# supply.net
KiCad netlist of a schematic drawn in Altium Designer
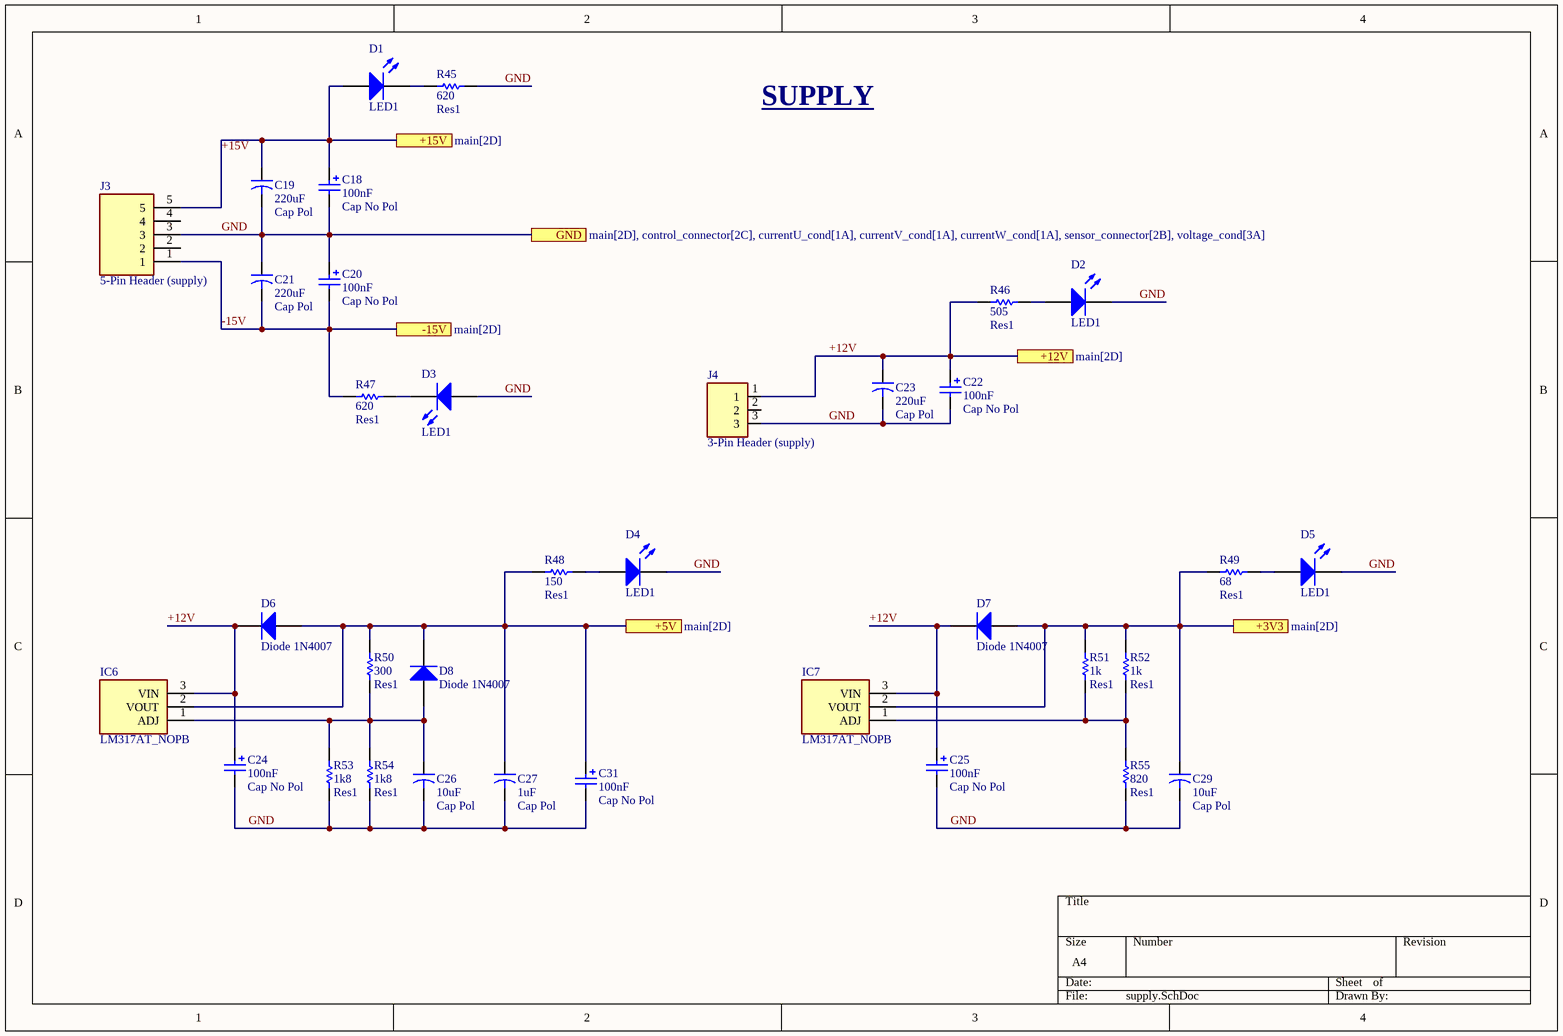
[diagram p0: supply.SchDoc]

(export (version "E")
  (design (tool "Eeschema 10.0.6"))
  (components
    (comp (ref "C18")
      (value "Cap No Pol")
      (footprint "RAD-0.1_mod")
      (description "Polarized Capacitor (Radial)")
      (fields (field (name "ALTIUM_VALUE") "100nF") (field (name "PUBLISHER") "Altium Limited"))
      (libsource (lib "LABSTEPS_Project") (part "Cap No Pol"))
    )
    (comp (ref "C19")
      (value "Cap Pol")
      (footprint "CAPR5-4X5_mod")
      (description "Capacitor")
      (fields (field (name "ALTIUM_VALUE") "220uF") (field (name "PUBLISHER") "Altium Limited"))
      (libsource (lib "LABSTEPS_Project") (part "Cap Pol"))
    )
    (comp (ref "C20")
      (value "Cap No Pol")
      (footprint "RAD-0.1_mod")
      (description "Polarized Capacitor (Radial)")
      (fields (field (name "ALTIUM_VALUE") "100nF") (field (name "PUBLISHER") "Altium Limited"))
      (libsource (lib "LABSTEPS_Project") (part "Cap No Pol"))
    )
    (comp (ref "C21")
      (value "Cap Pol")
      (footprint "CAPR5-4X5_mod")
      (description "Capacitor")
      (fields (field (name "ALTIUM_VALUE") "220uF") (field (name "PUBLISHER") "Altium Limited"))
      (libsource (lib "LABSTEPS_Project") (part "Cap Pol"))
    )
    (comp (ref "C22")
      (value "Cap No Pol")
      (footprint "RAD-0.1_mod")
      (description "Polarized Capacitor (Radial)")
      (fields (field (name "ALTIUM_VALUE") "100nF") (field (name "PUBLISHER") "Altium Limited"))
      (libsource (lib "LABSTEPS_Project") (part "Cap No Pol"))
    )
    (comp (ref "C23")
      (value "Cap Pol")
      (footprint "CAPR5-4X5_mod")
      (description "Capacitor")
      (fields (field (name "ALTIUM_VALUE") "220uF") (field (name "PUBLISHER") "Altium Limited"))
      (libsource (lib "LABSTEPS_Project") (part "Cap Pol"))
    )
    (comp (ref "C24")
      (value "Cap No Pol")
      (footprint "RAD-0.1_mod")
      (description "Polarized Capacitor (Radial)")
      (fields (field (name "ALTIUM_VALUE") "100nF") (field (name "PUBLISHER") "Altium Limited"))
      (libsource (lib "LABSTEPS_Project") (part "Cap No Pol"))
    )
    (comp (ref "C25")
      (value "Cap No Pol")
      (footprint "RAD-0.1_mod")
      (description "Polarized Capacitor (Radial)")
      (fields (field (name "ALTIUM_VALUE") "100nF") (field (name "PUBLISHER") "Altium Limited"))
      (libsource (lib "LABSTEPS_Project") (part "Cap No Pol"))
    )
    (comp (ref "C26")
      (value "Cap Pol")
      (footprint "CAPR5-4X5_mod")
      (description "Capacitor")
      (fields (field (name "ALTIUM_VALUE") "10uF") (field (name "PUBLISHER") "Altium Limited"))
      (libsource (lib "LABSTEPS_Project") (part "Cap Pol"))
    )
    (comp (ref "C27")
      (value "Cap Pol")
      (footprint "CAPR5-4X5_mod")
      (description "Capacitor")
      (fields (field (name "ALTIUM_VALUE") "1uF") (field (name "PUBLISHER") "Altium Limited"))
      (libsource (lib "LABSTEPS_Project") (part "Cap Pol"))
    )
    (comp (ref "C29")
      (value "Cap Pol")
      (footprint "CAPR5-4X5_mod")
      (description "Capacitor")
      (fields (field (name "ALTIUM_VALUE") "10uF") (field (name "PUBLISHER") "Altium Limited"))
      (libsource (lib "LABSTEPS_Project") (part "Cap Pol"))
    )
    (comp (ref "C31")
      (value "Cap No Pol")
      (footprint "RAD-0.1_mod")
      (description "Polarized Capacitor (Radial)")
      (fields (field (name "ALTIUM_VALUE") "100nF") (field (name "PUBLISHER") "Altium Limited"))
      (libsource (lib "LABSTEPS_Project") (part "Cap No Pol"))
    )
    (comp (ref "D1")
      (value "LED1")
      (footprint "PIN2_mod")
      (description "Typical RED GaAs LED")
      (fields (field (name "PUBLISHER") "Altium Limited"))
      (libsource (lib "moded_symbol") (part "LED1"))
    )
    (comp (ref "D2")
      (value "LED1")
      (footprint "PIN2_mod")
      (description "Typical RED GaAs LED")
      (fields (field (name "PUBLISHER") "Altium Limited"))
      (libsource (lib "moded_symbol") (part "LED1"))
    )
    (comp (ref "D3")
      (value "LED1")
      (footprint "PIN2_mod")
      (description "Typical RED GaAs LED")
      (fields (field (name "PUBLISHER") "Altium Limited"))
      (libsource (lib "moded_symbol") (part "LED1"))
    )
    (comp (ref "D4")
      (value "LED1")
      (footprint "PIN2_mod")
      (description "Typical RED GaAs LED")
      (fields (field (name "PUBLISHER") "Altium Limited"))
      (libsource (lib "moded_symbol") (part "LED1"))
    )
    (comp (ref "D5")
      (value "LED1")
      (footprint "PIN2_mod")
      (description "Typical RED GaAs LED")
      (fields (field (name "PUBLISHER") "Altium Limited"))
      (libsource (lib "moded_symbol") (part "LED1"))
    )
    (comp (ref "D6")
      (value "Diode 1N4007")
      (footprint "DO-41_mod")
      (description "1 Amp General Purpose Rectifier")
      (fields (field (name "PUBLISHER") "Altium Limited"))
      (libsource (lib "moded_symbol") (part "Diode 1N4007"))
    )
    (comp (ref "D7")
      (value "Diode 1N4007")
      (footprint "DO-41_mod")
      (description "1 Amp General Purpose Rectifier")
      (fields (field (name "PUBLISHER") "Altium Limited"))
      (libsource (lib "moded_symbol") (part "Diode 1N4007"))
    )
    (comp (ref "D8")
      (value "Diode 1N4007")
      (footprint "DO-41_mod")
      (description "1 Amp General Purpose Rectifier")
      (fields (field (name "PUBLISHER") "Altium Limited"))
      (libsource (lib "moded_symbol") (part "Diode 1N4007"))
    )
    (comp (ref "IC6")
      (value "LM317AT_NOPB")
      (footprint "TO254_mod")
      (description "Integrated Circuit")
      (fields
        (field (name "MANUFACTURER_PART_NUMBER") "LM317AT/NOPB")
        (field (name "MOUSER PART NUMBER") "926-LM317AT/NOPB")
      )
      (libsource (lib "SamacSys") (part "LM317AT_NOPB"))
    )
    (comp (ref "IC7")
      (value "LM317AT_NOPB")
      (footprint "TO254_mod")
      (description "Integrated Circuit")
      (fields
        (field (name "MANUFACTURER_PART_NUMBER") "LM317AT/NOPB")
        (field (name "MOUSER PART NUMBER") "926-LM317AT/NOPB")
      )
      (libsource (lib "SamacSys") (part "LM317AT_NOPB"))
    )
    (comp (ref "J3")
      (value "5-Pin Header (supply)")
      (footprint "MSTBA_5-PIN_HEADER_mod")
      (description "Pluggable Terminal Blocks MSTBA 2,5/ 5-G- 5,08 VPE250")
      (fields (field (name "MF") "Phoenix Contact") (field (name "MP") "1736175"))
      (libsource (lib "MSTBA_5-pin_header") (part "1736175"))
    )
    (comp (ref "J4")
      (value "3-Pin Header (supply)")
      (footprint "MSTBA_3-PIN_HEADER_mod")
      (fields (field (name "MP") "MSTBA 2,5/ 3-G-5,08 1757255") (field (name "MF") "Phoenix Contact"))
      (libsource (lib "MSTBA_3-pin_header") (part "MSTBA_2,5/_3-G-5,08_1757255"))
    )
    (comp (ref "R45")
      (value "Res1")
      (footprint "AXIAL-0.3_mod")
      (description "Resistor")
      (fields (field (name "ALTIUM_VALUE") "620") (field (name "PUBLISHER") "Altium Limited"))
      (libsource (lib "LABSTEPS_Project") (part "Res1"))
    )
    (comp (ref "R46")
      (value "Res1")
      (footprint "AXIAL-0.3_mod")
      (description "Resistor")
      (fields (field (name "ALTIUM_VALUE") "505") (field (name "PUBLISHER") "Altium Limited"))
      (libsource (lib "LABSTEPS_Project") (part "Res1"))
    )
    (comp (ref "R47")
      (value "Res1")
      (footprint "AXIAL-0.3_mod")
      (description "Resistor")
      (fields (field (name "ALTIUM_VALUE") "620") (field (name "PUBLISHER") "Altium Limited"))
      (libsource (lib "LABSTEPS_Project") (part "Res1"))
    )
    (comp (ref "R48")
      (value "Res1")
      (footprint "AXIAL-0.3_mod")
      (description "Resistor")
      (fields (field (name "ALTIUM_VALUE") "150") (field (name "PUBLISHER") "Altium Limited"))
      (libsource (lib "LABSTEPS_Project") (part "Res1"))
    )
    (comp (ref "R49")
      (value "Res1")
      (footprint "AXIAL-0.3_mod")
      (description "Resistor")
      (fields (field (name "ALTIUM_VALUE") "68") (field (name "PUBLISHER") "Altium Limited"))
      (libsource (lib "LABSTEPS_Project") (part "Res1"))
    )
    (comp (ref "R50")
      (value "Res1")
      (footprint "AXIAL-0.3_mod")
      (description "Resistor")
      (fields (field (name "ALTIUM_VALUE") "300") (field (name "PUBLISHER") "Altium Limited"))
      (libsource (lib "LABSTEPS_Project") (part "Res1"))
    )
    (comp (ref "R51")
      (value "Res1")
      (footprint "AXIAL-0.3_mod")
      (description "Resistor")
      (fields (field (name "ALTIUM_VALUE") "1k") (field (name "PUBLISHER") "Altium Limited"))
      (libsource (lib "LABSTEPS_Project") (part "Res1"))
    )
    (comp (ref "R52")
      (value "Res1")
      (footprint "AXIAL-0.3_mod")
      (description "Resistor")
      (fields (field (name "ALTIUM_VALUE") "1k") (field (name "PUBLISHER") "Altium Limited"))
      (libsource (lib "LABSTEPS_Project") (part "Res1"))
    )
    (comp (ref "R53")
      (value "Res1")
      (footprint "AXIAL-0.3_mod")
      (description "Resistor")
      (fields (field (name "ALTIUM_VALUE") "1k8") (field (name "PUBLISHER") "Altium Limited"))
      (libsource (lib "LABSTEPS_Project") (part "Res1"))
    )
    (comp (ref "R54")
      (value "Res1")
      (footprint "AXIAL-0.3_mod")
      (description "Resistor")
      (fields (field (name "ALTIUM_VALUE") "1k8") (field (name "PUBLISHER") "Altium Limited"))
      (libsource (lib "LABSTEPS_Project") (part "Res1"))
    )
    (comp (ref "R55")
      (value "Res1")
      (footprint "AXIAL-0.3_mod")
      (description "Resistor")
      (fields (field (name "ALTIUM_VALUE") "820") (field (name "PUBLISHER") "Altium Limited"))
      (libsource (lib "LABSTEPS_Project") (part "Res1"))
    )
  )
  (nets
    (net (code "1") (name "/+3V3") (class "Default")
      (node (ref "C29") (pin "1") (pinfunction "1_1") (pintype "passive"))
      (node (ref "D7") (pin "1") (pinfunction "A_1") (pintype "passive"))
      (node (ref "IC7") (pin "2") (pinfunction "VOUT_2") (pintype "passive"))
      (node (ref "R49") (pin "1") (pinfunction "1_1") (pintype "passive"))
      (node (ref "R51") (pin "1") (pinfunction "1_1") (pintype "passive"))
      (node (ref "R52") (pin "1") (pinfunction "1_1") (pintype "passive"))
    )
    (net (code "2") (name "/+5V") (class "Default")
      (node (ref "C27") (pin "1") (pinfunction "1_1") (pintype "passive"))
      (node (ref "C31") (pin "1") (pinfunction "1_1") (pintype "passive"))
      (node (ref "D6") (pin "1") (pinfunction "A_1") (pintype "passive"))
      (node (ref "D8") (pin "2") (pinfunction "K_2") (pintype "passive"))
      (node (ref "IC6") (pin "2") (pinfunction "VOUT_2") (pintype "passive"))
      (node (ref "R48") (pin "1") (pinfunction "1_1") (pintype "passive"))
      (node (ref "R50") (pin "1") (pinfunction "1_1") (pintype "passive"))
    )
    (net (code "3") (name "/+12V") (class "Default")
      (node (ref "C22") (pin "1") (pinfunction "1_1") (pintype "passive"))
      (node (ref "C23") (pin "1") (pinfunction "1_1") (pintype "passive"))
      (node (ref "C24") (pin "1") (pinfunction "1_1") (pintype "passive"))
      (node (ref "C25") (pin "1") (pinfunction "1_1") (pintype "passive"))
      (node (ref "D6") (pin "2") (pinfunction "K_2") (pintype "passive"))
      (node (ref "D7") (pin "2") (pinfunction "K_2") (pintype "passive"))
      (node (ref "IC6") (pin "3") (pinfunction "VIN_3") (pintype "passive"))
      (node (ref "IC7") (pin "3") (pinfunction "VIN_3") (pintype "passive"))
      (node (ref "J4") (pin "1") (pinfunction "1_1") (pintype "passive"))
      (node (ref "R46") (pin "1") (pinfunction "1_1") (pintype "passive"))
    )
    (net (code "4") (name "/+15V") (class "Default")
      (node (ref "C18") (pin "1") (pinfunction "1_1") (pintype "passive"))
      (node (ref "C19") (pin "1") (pinfunction "1_1") (pintype "passive"))
      (node (ref "D1") (pin "1") (pinfunction "A_1") (pintype "passive"))
      (node (ref "J3") (pin "5") (pinfunction "5_5") (pintype "passive"))
    )
    (net (code "5") (name "/-15V") (class "Default")
      (node (ref "C20") (pin "2") (pinfunction "2_2") (pintype "passive"))
      (node (ref "C21") (pin "2") (pinfunction "2_2") (pintype "passive"))
      (node (ref "J3") (pin "1") (pinfunction "1_1") (pintype "passive"))
      (node (ref "R47") (pin "2") (pinfunction "2_2") (pintype "passive"))
    )
    (net (code "6") (name "/GND") (class "Default")
      (node (ref "C18") (pin "2") (pinfunction "2_2") (pintype "passive"))
      (node (ref "C19") (pin "2") (pinfunction "2_2") (pintype "passive"))
      (node (ref "C20") (pin "1") (pinfunction "1_1") (pintype "passive"))
      (node (ref "C21") (pin "1") (pinfunction "1_1") (pintype "passive"))
      (node (ref "C22") (pin "2") (pinfunction "2_2") (pintype "passive"))
      (node (ref "C23") (pin "2") (pinfunction "2_2") (pintype "passive"))
      (node (ref "C24") (pin "2") (pinfunction "2_2") (pintype "passive"))
      (node (ref "C25") (pin "2") (pinfunction "2_2") (pintype "passive"))
      (node (ref "C26") (pin "2") (pinfunction "2_2") (pintype "passive"))
      (node (ref "C27") (pin "2") (pinfunction "2_2") (pintype "passive"))
      (node (ref "C29") (pin "2") (pinfunction "2_2") (pintype "passive"))
      (node (ref "C31") (pin "2") (pinfunction "2_2") (pintype "passive"))
      (node (ref "D2") (pin "2") (pinfunction "K_2") (pintype "passive"))
      (node (ref "D3") (pin "1") (pinfunction "A_1") (pintype "passive"))
      (node (ref "D4") (pin "2") (pinfunction "K_2") (pintype "passive"))
      (node (ref "D5") (pin "2") (pinfunction "K_2") (pintype "passive"))
      (node (ref "J3") (pin "3") (pinfunction "3_3") (pintype "passive"))
      (node (ref "J4") (pin "3") (pinfunction "3_3") (pintype "passive"))
      (node (ref "R45") (pin "2") (pinfunction "2_2") (pintype "passive"))
      (node (ref "R53") (pin "2") (pinfunction "2_2") (pintype "passive"))
      (node (ref "R54") (pin "2") (pinfunction "2_2") (pintype "passive"))
      (node (ref "R55") (pin "2") (pinfunction "2_2") (pintype "passive"))
    )
    (net (code "7") (name "Net-(D1-K)") (class "Default")
      (node (ref "D1") (pin "2") (pinfunction "K_2") (pintype "passive"))
      (node (ref "R45") (pin "1") (pinfunction "1_1") (pintype "passive"))
    )
    (net (code "8") (name "Net-(D2-A)") (class "Default")
      (node (ref "D2") (pin "1") (pinfunction "A_1") (pintype "passive"))
      (node (ref "R46") (pin "2") (pinfunction "2_2") (pintype "passive"))
    )
    (net (code "9") (name "Net-(D3-K)") (class "Default")
      (node (ref "D3") (pin "2") (pinfunction "K_2") (pintype "passive"))
      (node (ref "R47") (pin "1") (pinfunction "1_1") (pintype "passive"))
    )
    (net (code "10") (name "Net-(D4-A)") (class "Default")
      (node (ref "D4") (pin "1") (pinfunction "A_1") (pintype "passive"))
      (node (ref "R48") (pin "2") (pinfunction "2_2") (pintype "passive"))
    )
    (net (code "11") (name "Net-(D5-A)") (class "Default")
      (node (ref "D5") (pin "1") (pinfunction "A_1") (pintype "passive"))
      (node (ref "R49") (pin "2") (pinfunction "2_2") (pintype "passive"))
    )
    (net (code "12") (name "Net-(D8-A)") (class "Default")
      (node (ref "C26") (pin "1") (pinfunction "1_1") (pintype "passive"))
      (node (ref "D8") (pin "1") (pinfunction "A_1") (pintype "passive"))
      (node (ref "IC6") (pin "1") (pinfunction "ADJ_1") (pintype "passive"))
      (node (ref "R50") (pin "2") (pinfunction "2_2") (pintype "passive"))
      (node (ref "R53") (pin "1") (pinfunction "1_1") (pintype "passive"))
      (node (ref "R54") (pin "1") (pinfunction "1_1") (pintype "passive"))
    )
    (net (code "13") (name "Net-(IC7-ADJ)") (class "Default")
      (node (ref "IC7") (pin "1") (pinfunction "ADJ_1") (pintype "passive"))
      (node (ref "R51") (pin "2") (pinfunction "2_2") (pintype "passive"))
      (node (ref "R52") (pin "2") (pinfunction "2_2") (pintype "passive"))
      (node (ref "R55") (pin "1") (pinfunction "1_1") (pintype "passive"))
    )
    (net (code "14") (name "unconnected-(J3-Pad2)") (class "Default")
      (node (ref "J3") (pin "2") (pinfunction "2_2") (pintype "passive"))
    )
    (net (code "15") (name "unconnected-(J3-Pad4)") (class "Default")
      (node (ref "J3") (pin "4") (pinfunction "4_4") (pintype "passive"))
    )
    (net (code "16") (name "unconnected-(J4-Pad2)") (class "Default")
      (node (ref "J4") (pin "2") (pinfunction "2_2") (pintype "passive"))
    )
  )
)
